# primary_internship.net
KiCad netlist of a schematic drawn in Altium Designer
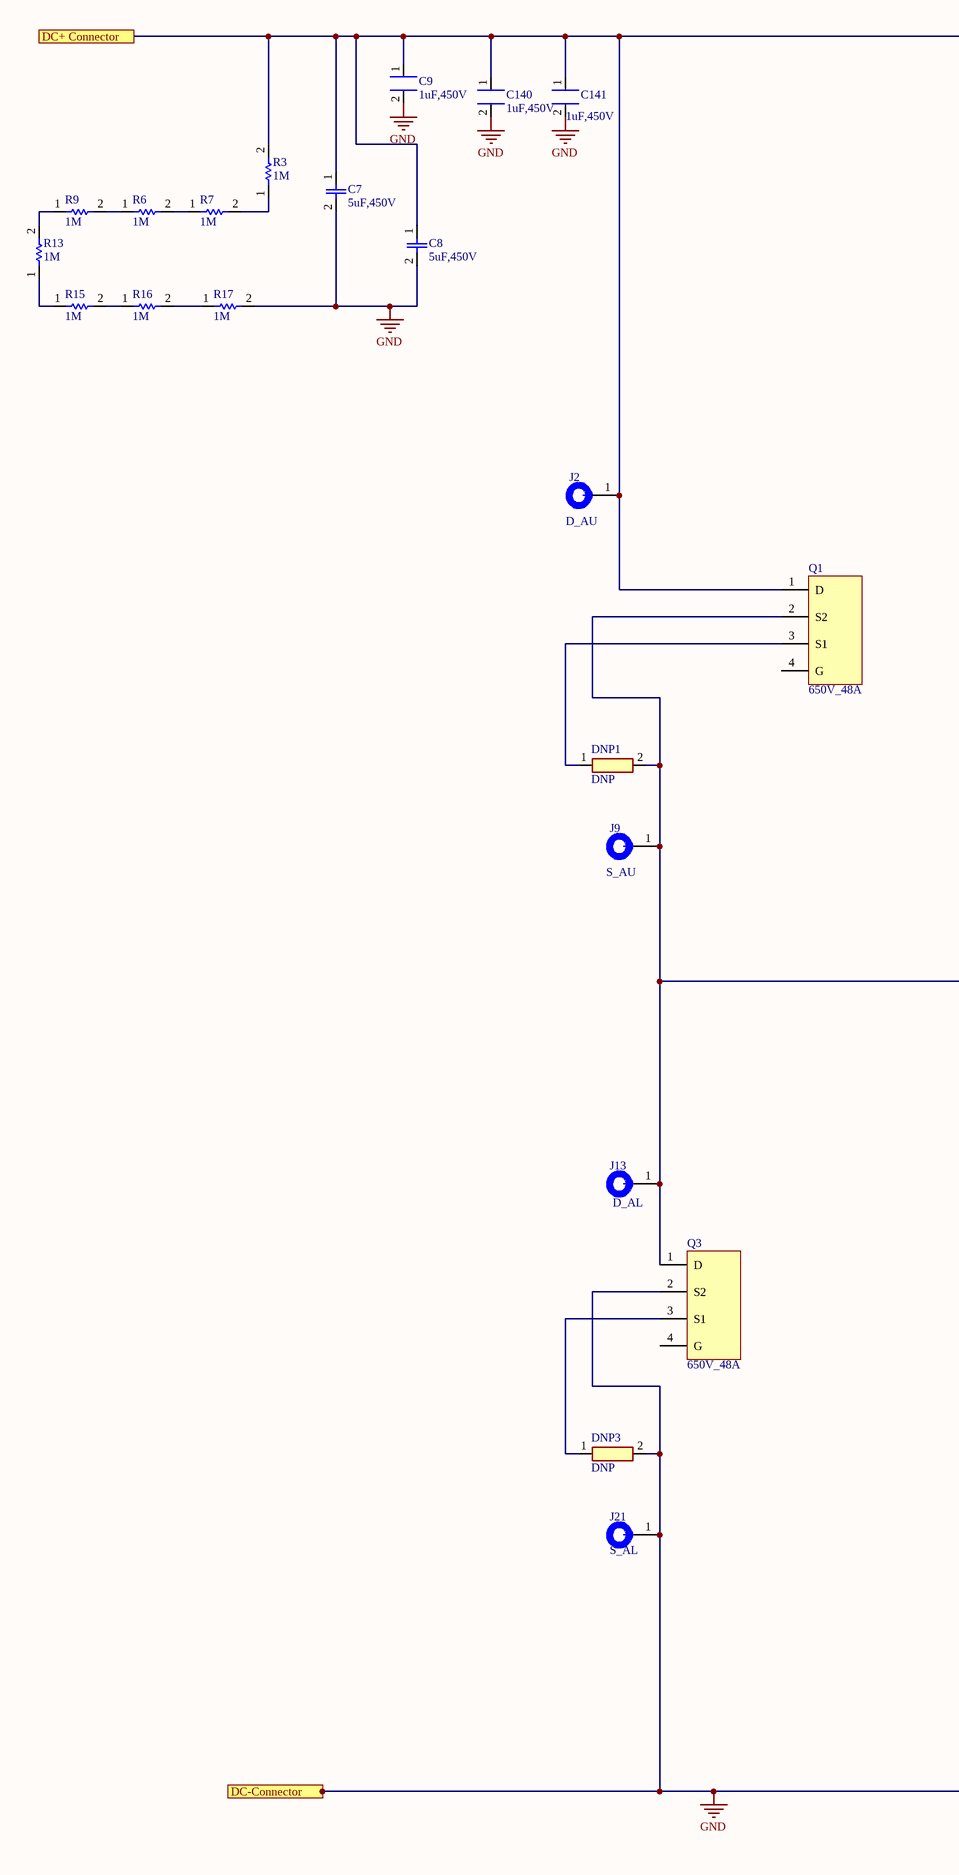
[diagram p0: primary_internship.SchDoc, left]
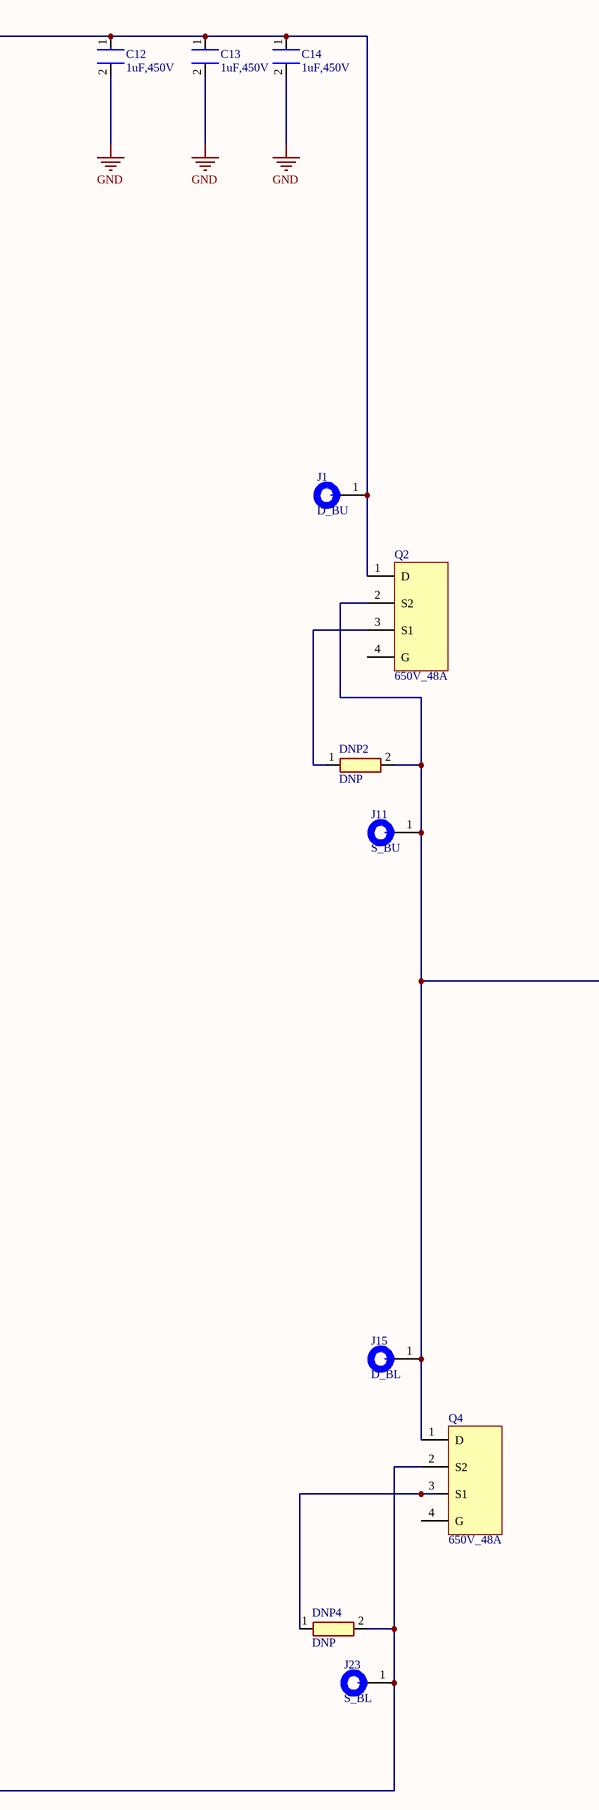
[diagram p1: primary_internship.SchDoc, right]

(export (version "E")
  (design (tool "Eeschema 10.0.6"))
  (components
    (comp (ref "C7")
      (value "5uF,450V")
      (footprint "CAP_B32774D4505K000_TDK")
      (description "5 µF Film Capacitor 450V Polypropylene (PP), Metallized Radial")
      (libsource (lib "Schlib_Internship") (part "B32774D4505K000"))
    )
    (comp (ref "C8")
      (value "5uF,450V")
      (footprint "CAP_B32774D4505K000_TDK")
      (description "5 µF Film Capacitor 450V Polypropylene (PP), Metallized Radial")
      (libsource (lib "Schlib_Internship") (part "B32774D4505K000"))
    )
    (comp (ref "C9")
      (value "1uF,450V")
      (footprint "CAP_5035_TDK")
      (description "1 µF ±20% 450V Ceramic Capacitor X7T Stacked SMD, 2 J-Lead")
      (libsource (lib "Schlib_Internship") (part "CKG45NX7T2W105M500JH"))
    )
    (comp (ref "C12")
      (value "1uF,450V")
      (footprint "CAP_5035_TDK")
      (description "1 µF ±20% 450V Ceramic Capacitor X7T Stacked SMD, 2 J-Lead")
      (libsource (lib "Schlib_Internship") (part "CKG45NX7T2W105M500JH"))
    )
    (comp (ref "C13")
      (value "1uF,450V")
      (footprint "CAP_5035_TDK")
      (description "1 µF ±20% 450V Ceramic Capacitor X7T Stacked SMD, 2 J-Lead")
      (libsource (lib "Schlib_Internship") (part "CKG45NX7T2W105M500JH"))
    )
    (comp (ref "C14")
      (value "1uF,450V")
      (footprint "CAP_5035_TDK")
      (description "1 µF ±20% 450V Ceramic Capacitor X7T Stacked SMD, 2 J-Lead")
      (libsource (lib "Schlib_Internship") (part "CKG45NX7T2W105M500JH"))
    )
    (comp (ref "C140")
      (value "1uF,450V")
      (footprint "CAP_5035_TDK")
      (description "1 µF ±20% 450V Ceramic Capacitor X7T Stacked SMD, 2 J-Lead")
      (libsource (lib "Schlib_Internship") (part "CKG45NX7T2W105M500JH"))
    )
    (comp (ref "C141")
      (value "1uF,450V")
      (footprint "CAP_5035_TDK")
      (description "1 µF ±20% 450V Ceramic Capacitor X7T Stacked SMD, 2 J-Lead")
      (libsource (lib "Schlib_Internship") (part "CKG45NX7T2W105M500JH"))
    )
    (comp (ref "DNP1")
      (value "DNP")
      (footprint "RC1206N_YAG")
      (description "8.2 Ohms ±1% 0.25W, 1/4W Chip Resistor 1206 (3216 Metric) Moisture Resistant Thick Film")
      (libsource (lib "Schlib_Internship") (part "RC1206FR-078R2L"))
    )
    (comp (ref "DNP2")
      (value "DNP")
      (footprint "RC1206N_YAG")
      (description "8.2 Ohms ±1% 0.25W, 1/4W Chip Resistor 1206 (3216 Metric) Moisture Resistant Thick Film")
      (libsource (lib "Schlib_Internship") (part "RC1206FR-078R2L"))
    )
    (comp (ref "DNP3")
      (value "DNP")
      (footprint "RC1206N_YAG")
      (description "8.2 Ohms ±1% 0.25W, 1/4W Chip Resistor 1206 (3216 Metric) Moisture Resistant Thick Film")
      (libsource (lib "Schlib_Internship") (part "RC1206FR-078R2L"))
    )
    (comp (ref "DNP4")
      (value "DNP")
      (footprint "RC1206N_YAG")
      (description "8.2 Ohms ±1% 0.25W, 1/4W Chip Resistor 1206 (3216 Metric) Moisture Resistant Thick Film")
      (libsource (lib "Schlib_Internship") (part "RC1206FR-078R2L"))
    )
    (comp (ref "J1")
      (value "D_BU")
      (footprint "FP-S2751-46R-MFG")
      (description "PC TEST POINT NATURAL")
      (libsource (lib "Schlib_Internship") (part "CMP-15817-000010-1"))
    )
    (comp (ref "J2")
      (value "D_AU")
      (footprint "FP-S2751-46R-MFG")
      (description "PC TEST POINT NATURAL")
      (libsource (lib "Schlib_Internship") (part "CMP-15817-000010-1"))
    )
    (comp (ref "J9")
      (value "S_AU")
      (footprint "FP-S2751-46R-MFG")
      (description "PC TEST POINT NATURAL")
      (libsource (lib "Schlib_Internship") (part "CMP-15817-000010-1"))
    )
    (comp (ref "J11")
      (value "S_BU")
      (footprint "FP-S2751-46R-MFG")
      (description "PC TEST POINT NATURAL")
      (libsource (lib "Schlib_Internship") (part "CMP-15817-000010-1"))
    )
    (comp (ref "J13")
      (value "D_AL")
      (footprint "FP-S2751-46R-MFG")
      (description "PC TEST POINT NATURAL")
      (libsource (lib "Schlib_Internship") (part "CMP-15817-000010-1"))
    )
    (comp (ref "J15")
      (value "D_BL")
      (footprint "FP-S2751-46R-MFG")
      (description "PC TEST POINT NATURAL")
      (libsource (lib "Schlib_Internship") (part "CMP-15817-000010-1"))
    )
    (comp (ref "J21")
      (value "S_AL")
      (footprint "FP-S2751-46R-MFG")
      (description "PC TEST POINT NATURAL")
      (libsource (lib "Schlib_Internship") (part "CMP-15817-000010-1"))
    )
    (comp (ref "J23")
      (value "S_BL")
      (footprint "FP-S2751-46R-MFG")
      (description "PC TEST POINT NATURAL")
      (libsource (lib "Schlib_Internship") (part "CMP-15817-000010-1"))
    )
    (comp (ref "Q1")
      (value "650V_48A")
      (description "N-Channel 650 V 47A (Tc) 176W (Tc) Through Hole TO-247-4L")
      (libsource (lib "Schlib_Internship") (part "SIC MOS TO247-4L 650V"))
    )
    (comp (ref "Q2")
      (value "650V_48A")
      (description "N-Channel 650 V 47A (Tc) 176W (Tc) Through Hole TO-247-4L")
      (libsource (lib "Schlib_Internship") (part "SIC MOS TO247-4L 650V"))
    )
    (comp (ref "Q3")
      (value "650V_48A")
      (description "N-Channel 650 V 47A (Tc) 176W (Tc) Through Hole TO-247-4L")
      (libsource (lib "Schlib_Internship") (part "SIC MOS TO247-4L 650V"))
    )
    (comp (ref "Q4")
      (value "650V_48A")
      (description "N-Channel 650 V 47A (Tc) 176W (Tc) Through Hole TO-247-4L")
      (libsource (lib "Schlib_Internship") (part "SIC MOS TO247-4L 650V"))
    )
    (comp (ref "R3")
      (value "1M")
      (footprint "RESC3216X70X50LL05T20")
      (description "Thick Film Resistors - SMD 1206 1Mohms 1% Tol AEC-Q200")
      (fields (field (name "MANUFACTURER") "Panasonic") (field (name "PART NUMBER") "ERJ-8ENF3321V"))
      (libsource (lib "Schlib_Internship") (part "CMP-2003-00309-1"))
    )
    (comp (ref "R6")
      (value "1M")
      (footprint "RESC3216X70X50LL05T20")
      (description "Thick Film Resistors - SMD 1206 1Mohms 1% Tol AEC-Q200")
      (fields (field (name "MANUFACTURER") "Panasonic") (field (name "PART NUMBER") "ERJ-8ENF3321V"))
      (libsource (lib "Schlib_Internship") (part "CMP-2003-00309-1"))
    )
    (comp (ref "R7")
      (value "1M")
      (footprint "RESC3216X70X50LL05T20")
      (description "Thick Film Resistors - SMD 1206 1Mohms 1% Tol AEC-Q200")
      (fields (field (name "MANUFACTURER") "Panasonic") (field (name "PART NUMBER") "ERJ-8ENF3321V"))
      (libsource (lib "Schlib_Internship") (part "CMP-2003-00309-1"))
    )
    (comp (ref "R9")
      (value "1M")
      (footprint "RESC3216X70X50LL05T20")
      (description "Thick Film Resistors - SMD 1206 1Mohms 1% Tol AEC-Q200")
      (fields (field (name "MANUFACTURER") "Panasonic") (field (name "PART NUMBER") "ERJ-8ENF3321V"))
      (libsource (lib "Schlib_Internship") (part "CMP-2003-00309-1"))
    )
    (comp (ref "R13")
      (value "1M")
      (footprint "RESC3216X70X50LL05T20")
      (description "Thick Film Resistors - SMD 1206 1Mohms 1% Tol AEC-Q200")
      (fields (field (name "MANUFACTURER") "Panasonic") (field (name "PART NUMBER") "ERJ-8ENF3321V"))
      (libsource (lib "Schlib_Internship") (part "CMP-2003-00309-1"))
    )
    (comp (ref "R15")
      (value "1M")
      (footprint "RESC3216X70X50LL05T20")
      (description "Thick Film Resistors - SMD 1206 1Mohms 1% Tol AEC-Q200")
      (fields (field (name "MANUFACTURER") "Panasonic") (field (name "PART NUMBER") "ERJ-8ENF3321V"))
      (libsource (lib "Schlib_Internship") (part "CMP-2003-00309-1"))
    )
    (comp (ref "R16")
      (value "1M")
      (footprint "RESC3216X70X50LL05T20")
      (description "Thick Film Resistors - SMD 1206 1Mohms 1% Tol AEC-Q200")
      (fields (field (name "MANUFACTURER") "Panasonic") (field (name "PART NUMBER") "ERJ-8ENF3321V"))
      (libsource (lib "Schlib_Internship") (part "CMP-2003-00309-1"))
    )
    (comp (ref "R17")
      (value "1M")
      (footprint "RESC3216X70X50LL05T20")
      (description "Thick Film Resistors - SMD 1206 1Mohms 1% Tol AEC-Q200")
      (fields (field (name "MANUFACTURER") "Panasonic") (field (name "PART NUMBER") "ERJ-8ENF3321V"))
      (libsource (lib "Schlib_Internship") (part "CMP-2003-00309-1"))
    )
  )
  (nets
    (net (code "1") (name "/DC+ Connector") (class "Default")
      (node (ref "C12") (pin "1") (pinfunction "1_1") (pintype "passive"))
      (node (ref "C13") (pin "1") (pinfunction "1_1") (pintype "passive"))
      (node (ref "C14") (pin "1") (pinfunction "1_1") (pintype "passive"))
      (node (ref "C140") (pin "1") (pinfunction "1_1") (pintype "passive"))
      (node (ref "C141") (pin "1") (pinfunction "1_1") (pintype "passive"))
      (node (ref "C7") (pin "1") (pinfunction "1_1") (pintype "passive"))
      (node (ref "C8") (pin "1") (pinfunction "1_1") (pintype "passive"))
      (node (ref "C9") (pin "1") (pinfunction "1_1") (pintype "passive"))
      (node (ref "J1") (pin "1") (pinfunction "1_1") (pintype "passive"))
      (node (ref "J2") (pin "1") (pinfunction "1_1") (pintype "passive"))
      (node (ref "Q1") (pin "1") (pinfunction "D_1") (pintype "passive"))
      (node (ref "Q2") (pin "1") (pinfunction "D_1") (pintype "passive"))
      (node (ref "R3") (pin "2") (pinfunction "2_2") (pintype "passive"))
    )
    (net (code "2") (name "GND") (class "Default")
      (node (ref "C12") (pin "2") (pinfunction "2_2") (pintype "passive"))
      (node (ref "C13") (pin "2") (pinfunction "2_2") (pintype "passive"))
      (node (ref "C14") (pin "2") (pinfunction "2_2") (pintype "passive"))
      (node (ref "C140") (pin "2") (pinfunction "2_2") (pintype "passive"))
      (node (ref "C141") (pin "2") (pinfunction "2_2") (pintype "passive"))
      (node (ref "C7") (pin "2") (pinfunction "2_2") (pintype "passive"))
      (node (ref "C8") (pin "2") (pinfunction "2_2") (pintype "passive"))
      (node (ref "C9") (pin "2") (pinfunction "2_2") (pintype "passive"))
      (node (ref "DNP3") (pin "2") (pinfunction "2_2") (pintype "passive"))
      (node (ref "DNP4") (pin "2") (pinfunction "2_2") (pintype "passive"))
      (node (ref "J21") (pin "1") (pinfunction "1_1") (pintype "passive"))
      (node (ref "J23") (pin "1") (pinfunction "1_1") (pintype "passive"))
      (node (ref "Q3") (pin "2") (pinfunction "S2_2") (pintype "passive"))
      (node (ref "Q4") (pin "2") (pinfunction "S2_2") (pintype "passive"))
      (node (ref "R17") (pin "2") (pinfunction "2_2") (pintype "passive"))
    )
    (net (code "3") (name "Net-(Q1-S1)") (class "Default")
      (node (ref "DNP1") (pin "1") (pinfunction "1_1") (pintype "passive"))
      (node (ref "Q1") (pin "3") (pinfunction "S1_3") (pintype "passive"))
    )
    (net (code "4") (name "Net-(Q1-S2)") (class "Default")
      (node (ref "DNP1") (pin "2") (pinfunction "2_2") (pintype "passive"))
      (node (ref "J13") (pin "1") (pinfunction "1_1") (pintype "passive"))
      (node (ref "J9") (pin "1") (pinfunction "1_1") (pintype "passive"))
      (node (ref "Q1") (pin "2") (pinfunction "S2_2") (pintype "passive"))
      (node (ref "Q3") (pin "1") (pinfunction "D_1") (pintype "passive"))
    )
    (net (code "5") (name "Net-(Q2-S1)") (class "Default")
      (node (ref "DNP2") (pin "1") (pinfunction "1_1") (pintype "passive"))
      (node (ref "Q2") (pin "3") (pinfunction "S1_3") (pintype "passive"))
    )
    (net (code "6") (name "Net-(Q2-S2)") (class "Default")
      (node (ref "DNP2") (pin "2") (pinfunction "2_2") (pintype "passive"))
      (node (ref "J11") (pin "1") (pinfunction "1_1") (pintype "passive"))
      (node (ref "J15") (pin "1") (pinfunction "1_1") (pintype "passive"))
      (node (ref "Q2") (pin "2") (pinfunction "S2_2") (pintype "passive"))
      (node (ref "Q4") (pin "1") (pinfunction "D_1") (pintype "passive"))
    )
    (net (code "7") (name "Net-(Q3-S1)") (class "Default")
      (node (ref "DNP3") (pin "1") (pinfunction "1_1") (pintype "passive"))
      (node (ref "Q3") (pin "3") (pinfunction "S1_3") (pintype "passive"))
    )
    (net (code "8") (name "Net-(Q4-S1)") (class "Default")
      (node (ref "DNP4") (pin "1") (pinfunction "1_1") (pintype "passive"))
      (node (ref "Q4") (pin "3") (pinfunction "S1_3") (pintype "passive"))
    )
    (net (code "9") (name "Net-(R3-Pad1)") (class "Default")
      (node (ref "R3") (pin "1") (pinfunction "1_1") (pintype "passive"))
      (node (ref "R7") (pin "2") (pinfunction "2_2") (pintype "passive"))
    )
    (net (code "10") (name "Net-(R6-Pad1)") (class "Default")
      (node (ref "R6") (pin "1") (pinfunction "1_1") (pintype "passive"))
      (node (ref "R9") (pin "2") (pinfunction "2_2") (pintype "passive"))
    )
    (net (code "11") (name "Net-(R6-Pad2)") (class "Default")
      (node (ref "R6") (pin "2") (pinfunction "2_2") (pintype "passive"))
      (node (ref "R7") (pin "1") (pinfunction "1_1") (pintype "passive"))
    )
    (net (code "12") (name "Net-(R13-Pad1)") (class "Default")
      (node (ref "R13") (pin "1") (pinfunction "1_1") (pintype "passive"))
      (node (ref "R15") (pin "1") (pinfunction "1_1") (pintype "passive"))
    )
    (net (code "13") (name "Net-(R13-Pad2)") (class "Default")
      (node (ref "R13") (pin "2") (pinfunction "2_2") (pintype "passive"))
      (node (ref "R9") (pin "1") (pinfunction "1_1") (pintype "passive"))
    )
    (net (code "14") (name "Net-(R15-Pad2)") (class "Default")
      (node (ref "R15") (pin "2") (pinfunction "2_2") (pintype "passive"))
      (node (ref "R16") (pin "1") (pinfunction "1_1") (pintype "passive"))
    )
    (net (code "15") (name "Net-(R16-Pad2)") (class "Default")
      (node (ref "R16") (pin "2") (pinfunction "2_2") (pintype "passive"))
      (node (ref "R17") (pin "1") (pinfunction "1_1") (pintype "passive"))
    )
    (net (code "16") (name "unconnected-(Q1-G-Pad4)") (class "Default")
      (node (ref "Q1") (pin "4") (pinfunction "G_4") (pintype "passive"))
    )
    (net (code "17") (name "unconnected-(Q2-G-Pad4)") (class "Default")
      (node (ref "Q2") (pin "4") (pinfunction "G_4") (pintype "passive"))
    )
    (net (code "18") (name "unconnected-(Q3-G-Pad4)") (class "Default")
      (node (ref "Q3") (pin "4") (pinfunction "G_4") (pintype "passive"))
    )
    (net (code "19") (name "unconnected-(Q4-G-Pad4)") (class "Default")
      (node (ref "Q4") (pin "4") (pinfunction "G_4") (pintype "passive"))
    )
  )
)
